# x-IMU3-SA-A8.net
KiCad netlist of a schematic drawn in Altium Designer
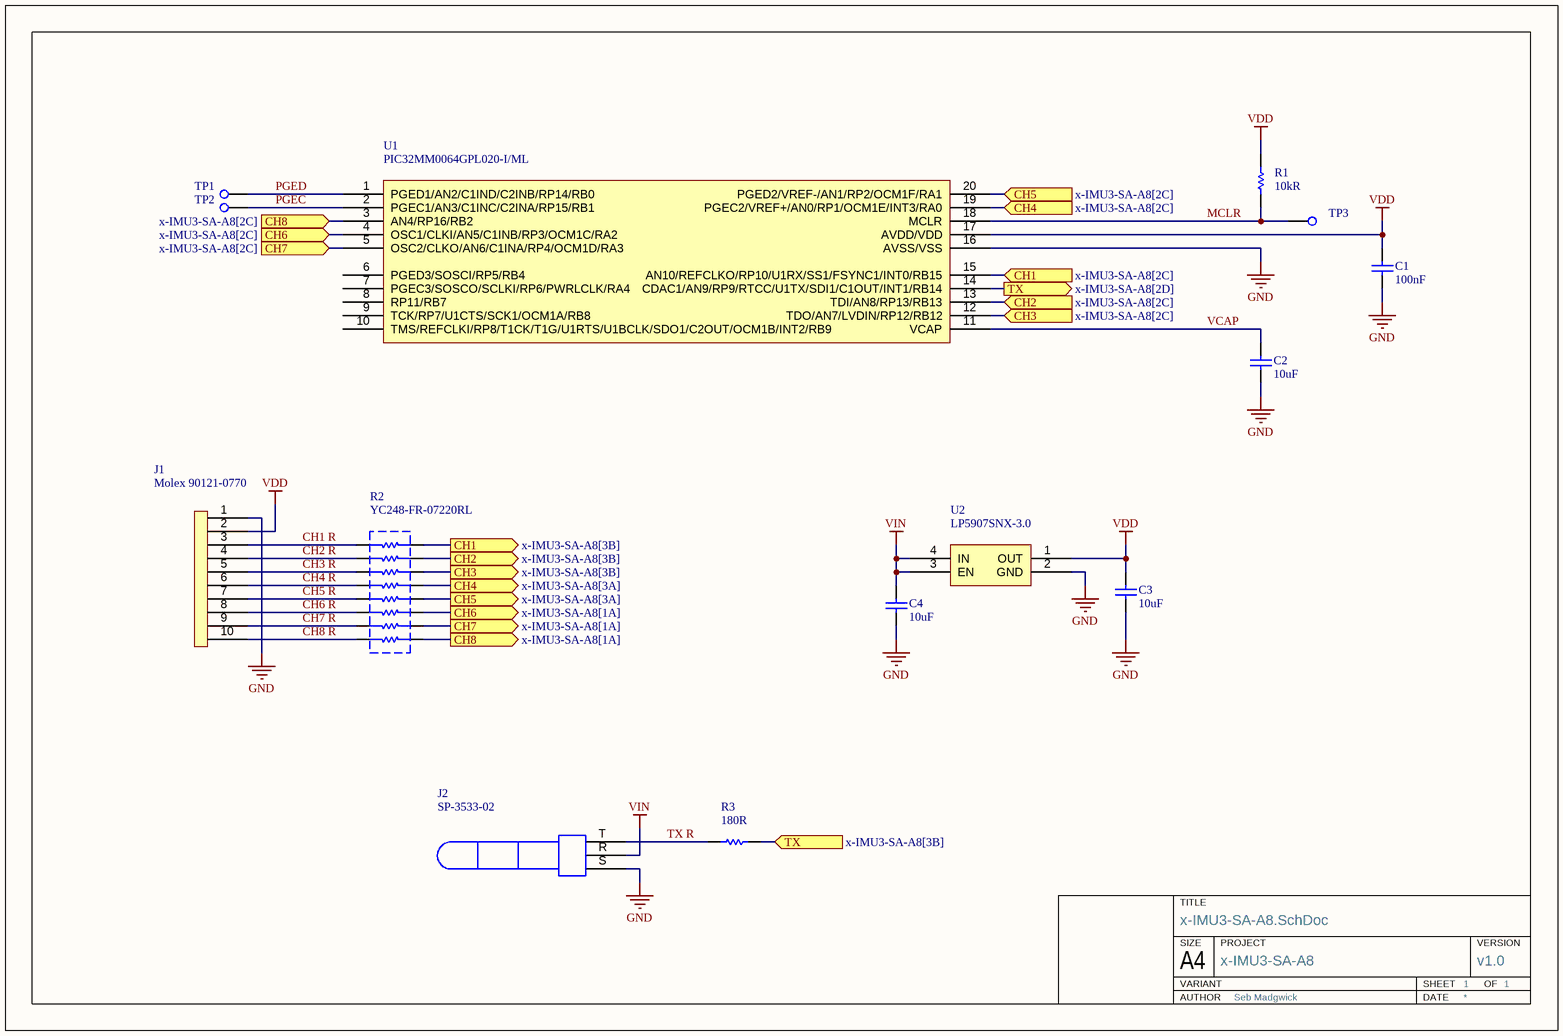
[diagram p0: x-IMU3-SA-A8.SchDoc]

(export (version "E")
  (design (tool "Eeschema 10.0.6"))
  (components
    (comp (ref "C1") (value "100nF") (footprint "Capacitor 0402") (libsource (lib "x-io") (part "Capacitor")))
    (comp (ref "C2") (value "10uF") (footprint "Capacitor 0402") (libsource (lib "x-io") (part "Capacitor")))
    (comp (ref "C3") (value "10uF") (footprint "Capacitor 0402") (libsource (lib "x-io") (part "Capacitor")))
    (comp (ref "C4") (value "10uF") (footprint "Capacitor 0402") (libsource (lib "x-io") (part "Capacitor")))
    (comp (ref "J1")
      (value "Molex 90121-0770")
      (footprint "Molex 90121-0770")
      (libsource (lib "x-io") (part "Molex 90121-0770"))
    )
    (comp (ref "J2")
      (value "SP-3533-02")
      (footprint "SP-3533-02")
      (libsource (lib "x-io") (part "SP-3533-02"))
    )
    (comp (ref "R1") (value "10kR") (footprint "Resistor 0402") (libsource (lib "x-io") (part "Resistor")))
    (comp (ref "R2")
      (value "YC248-FR-07220RL")
      (footprint "YC248")
      (libsource (lib "x-io") (part "Resistor Array 8"))
    )
    (comp (ref "R3") (value "180R") (footprint "Resistor 0402") (libsource (lib "x-io") (part "Resistor")))
    (comp (ref "TP1")
      (value "Test Point")
      (footprint "Test Point 1mm")
      (libsource (lib "x-io") (part "Test Point"))
    )
    (comp (ref "TP2")
      (value "Test Point")
      (footprint "Test Point 1mm")
      (libsource (lib "x-io") (part "Test Point"))
    )
    (comp (ref "TP3")
      (value "Test Point")
      (footprint "Test Point 1mm")
      (libsource (lib "x-io") (part "Test Point"))
    )
    (comp (ref "U1")
      (value "PIC32MM0064GPL020-I/ML")
      (footprint "QFN-20")
      (libsource (lib "x-io") (part "PIC32MM0064GPL020-I/ML"))
    )
    (comp (ref "U2")
      (value "LP5907SNX-3.0")
      (footprint "X2SON")
      (libsource (lib "x-io") (part "LP5907SNX-X.X"))
    )
  )
  (nets
    (net (code "1") (name "/CH1") (class "Default")
      (node (ref "R2") (pin "1") (pinfunction "1_1") (pintype "passive"))
      (node (ref "U1") (pin "15") (pinfunction "AN10/REFCLKO/RP10/U1RX/SS1/FSYNC1/INT0/RB15_15") (pintype "passive"))
    )
    (net (code "2") (name "/CH1 R") (class "Default")
      (node (ref "J1") (pin "3") (pinfunction "3_3") (pintype "passive"))
      (node (ref "R2") (pin "16") (pinfunction "16_16") (pintype "passive"))
    )
    (net (code "3") (name "/CH2") (class "Default")
      (node (ref "R2") (pin "2") (pinfunction "2_2") (pintype "passive"))
      (node (ref "U1") (pin "13") (pinfunction "TDI/AN8/RP13/RB13_13") (pintype "passive"))
    )
    (net (code "4") (name "/CH2 R") (class "Default")
      (node (ref "J1") (pin "4") (pinfunction "4_4") (pintype "passive"))
      (node (ref "R2") (pin "15") (pinfunction "15_15") (pintype "passive"))
    )
    (net (code "5") (name "/CH3") (class "Default")
      (node (ref "R2") (pin "3") (pinfunction "3_3") (pintype "passive"))
      (node (ref "U1") (pin "12") (pinfunction "TDO/AN7/LVDIN/RP12/RB12_12") (pintype "passive"))
    )
    (net (code "6") (name "/CH3 R") (class "Default")
      (node (ref "J1") (pin "5") (pinfunction "5_5") (pintype "passive"))
      (node (ref "R2") (pin "14") (pinfunction "14_14") (pintype "passive"))
    )
    (net (code "7") (name "/CH4") (class "Default")
      (node (ref "R2") (pin "4") (pinfunction "4_4") (pintype "passive"))
      (node (ref "U1") (pin "19") (pinfunction "PGEC2/VREF+/AN0/RP1/OCM1E/INT3/RA0_19") (pintype "passive"))
    )
    (net (code "8") (name "/CH4 R") (class "Default")
      (node (ref "J1") (pin "6") (pinfunction "6_6") (pintype "passive"))
      (node (ref "R2") (pin "13") (pinfunction "13_13") (pintype "passive"))
    )
    (net (code "9") (name "/CH5") (class "Default")
      (node (ref "R2") (pin "5") (pinfunction "5_5") (pintype "passive"))
      (node (ref "U1") (pin "20") (pinfunction "PGED2/VREF-/AN1/RP2/OCM1F/RA1_20") (pintype "passive"))
    )
    (net (code "10") (name "/CH5 R") (class "Default")
      (node (ref "J1") (pin "7") (pinfunction "7_7") (pintype "passive"))
      (node (ref "R2") (pin "12") (pinfunction "12_12") (pintype "passive"))
    )
    (net (code "11") (name "/CH6") (class "Default")
      (node (ref "R2") (pin "6") (pinfunction "6_6") (pintype "passive"))
      (node (ref "U1") (pin "4") (pinfunction "OSC1/CLKI/AN5/C1INB/RP3/OCM1C/RA2_4") (pintype "passive"))
    )
    (net (code "12") (name "/CH6 R") (class "Default")
      (node (ref "J1") (pin "8") (pinfunction "8_8") (pintype "passive"))
      (node (ref "R2") (pin "11") (pinfunction "11_11") (pintype "passive"))
    )
    (net (code "13") (name "/CH7") (class "Default")
      (node (ref "R2") (pin "7") (pinfunction "7_7") (pintype "passive"))
      (node (ref "U1") (pin "5") (pinfunction "OSC2/CLKO/AN6/C1INA/RP4/OCM1D/RA3_5") (pintype "passive"))
    )
    (net (code "14") (name "/CH7 R") (class "Default")
      (node (ref "J1") (pin "9") (pinfunction "9_9") (pintype "passive"))
      (node (ref "R2") (pin "10") (pinfunction "10_10") (pintype "passive"))
    )
    (net (code "15") (name "/CH8") (class "Default")
      (node (ref "R2") (pin "8") (pinfunction "8_8") (pintype "passive"))
      (node (ref "U1") (pin "3") (pinfunction "AN4/RP16/RB2_3") (pintype "passive"))
    )
    (net (code "16") (name "/CH8 R") (class "Default")
      (node (ref "J1") (pin "10") (pinfunction "10_10") (pintype "passive"))
      (node (ref "R2") (pin "9") (pinfunction "9_9") (pintype "passive"))
    )
    (net (code "17") (name "/MCLR") (class "Default")
      (node (ref "R1") (pin "1") (pinfunction "1_1") (pintype "passive"))
      (node (ref "TP3") (pin "1") (pinfunction "1_1") (pintype "passive"))
      (node (ref "U1") (pin "18") (pinfunction "MCLR_18") (pintype "passive"))
    )
    (net (code "18") (name "/PGEC") (class "Default")
      (node (ref "TP2") (pin "1") (pinfunction "1_1") (pintype "passive"))
      (node (ref "U1") (pin "2") (pinfunction "PGEC1/AN3/C1INC/C2INA/RP15/RB1_2") (pintype "passive"))
    )
    (net (code "19") (name "/PGED") (class "Default")
      (node (ref "TP1") (pin "1") (pinfunction "1_1") (pintype "passive"))
      (node (ref "U1") (pin "1") (pinfunction "PGED1/AN2/C1IND/C2INB/RP14/RB0_1") (pintype "passive"))
    )
    (net (code "20") (name "/TX") (class "Default")
      (node (ref "R3") (pin "2") (pinfunction "2_2") (pintype "passive"))
      (node (ref "U1") (pin "14") (pinfunction "CDAC1/AN9/RP9/RTCC/U1TX/SDI1/C1OUT/INT1/RB14_14") (pintype "passive"))
    )
    (net (code "21") (name "/TX R") (class "Default")
      (node (ref "J2") (pin "T") (pinfunction "T_T") (pintype "passive"))
      (node (ref "R3") (pin "1") (pinfunction "1_1") (pintype "passive"))
    )
    (net (code "22") (name "/VCAP") (class "Default")
      (node (ref "C2") (pin "2") (pinfunction "2_2") (pintype "passive"))
      (node (ref "U1") (pin "11") (pinfunction "VCAP_11") (pintype "passive"))
    )
    (net (code "23") (name "GND") (class "Default")
      (node (ref "C1") (pin "1") (pinfunction "1_1") (pintype "passive"))
      (node (ref "C2") (pin "1") (pinfunction "1_1") (pintype "passive"))
      (node (ref "C3") (pin "1") (pinfunction "1_1") (pintype "passive"))
      (node (ref "C4") (pin "1") (pinfunction "1_1") (pintype "passive"))
      (node (ref "J1") (pin "1") (pinfunction "1_1") (pintype "passive"))
      (node (ref "J2") (pin "S") (pinfunction "S_S") (pintype "passive"))
      (node (ref "U1") (pin "16") (pinfunction "AVSS/VSS_16") (pintype "passive"))
      (node (ref "U2") (pin "2") (pinfunction "GND_2") (pintype "passive"))
    )
    (net (code "24") (name "VDD") (class "Default")
      (node (ref "C1") (pin "2") (pinfunction "2_2") (pintype "passive"))
      (node (ref "C3") (pin "2") (pinfunction "2_2") (pintype "passive"))
      (node (ref "J1") (pin "2") (pinfunction "2_2") (pintype "passive"))
      (node (ref "R1") (pin "2") (pinfunction "2_2") (pintype "passive"))
      (node (ref "U1") (pin "17") (pinfunction "AVDD/VDD_17") (pintype "passive"))
      (node (ref "U2") (pin "1") (pinfunction "OUT_1") (pintype "passive"))
    )
    (net (code "25") (name "VIN") (class "Default")
      (node (ref "C4") (pin "2") (pinfunction "2_2") (pintype "passive"))
      (node (ref "J2") (pin "R") (pinfunction "R_R") (pintype "passive"))
      (node (ref "U2") (pin "3") (pinfunction "EN_3") (pintype "passive"))
      (node (ref "U2") (pin "4") (pinfunction "IN_4") (pintype "passive"))
    )
    (net (code "26") (name "unconnected-(U1-PGEC3{slash}SOSCO{slash}SCLKI{slash}RP6{slash}PWRLCLK{slash}RA4-Pad7)") (class "Default")
      (node (ref "U1") (pin "7") (pinfunction "PGEC3/SOSCO/SCLKI/RP6/PWRLCLK/RA4_7") (pintype "passive"))
    )
    (net (code "27") (name "unconnected-(U1-PGED3{slash}SOSCI{slash}RP5{slash}RB4-Pad6)") (class "Default")
      (node (ref "U1") (pin "6") (pinfunction "PGED3/SOSCI/RP5/RB4_6") (pintype "passive"))
    )
    (net (code "28") (name "unconnected-(U1-RP11{slash}RB7-Pad8)") (class "Default")
      (node (ref "U1") (pin "8") (pinfunction "RP11/RB7_8") (pintype "passive"))
    )
    (net (code "29") (name "unconnected-(U1-TCK{slash}RP7{slash}U1CTS{slash}SCK1{slash}OCM1A{slash}RB8-Pad9)") (class "Default")
      (node (ref "U1") (pin "9") (pinfunction "TCK/RP7/U1CTS/SCK1/OCM1A/RB8_9") (pintype "passive"))
    )
    (net (code "30") (name "unconnected-(U1-TMS{slash}REFCLKI{slash}RP8{slash}T1CK{slash}T1G{slash}U1RTS{slash}U1BCLK{slash}SDO1{slash}C2OUT{slash}OCM1B{slash}INT2{slash}RB9-Pad10)") (class "Default")
      (node (ref "U1") (pin "10") (pinfunction "TMS/REFCLKI/RP8/T1CK/T1G/U1RTS/U1BCLK/SDO1/C2OUT/OCM1B/INT2/RB9_10") (pintype "passive"))
    )
  )
)
